# Blinky.net
KiCad netlist of a schematic drawn in EAGLE
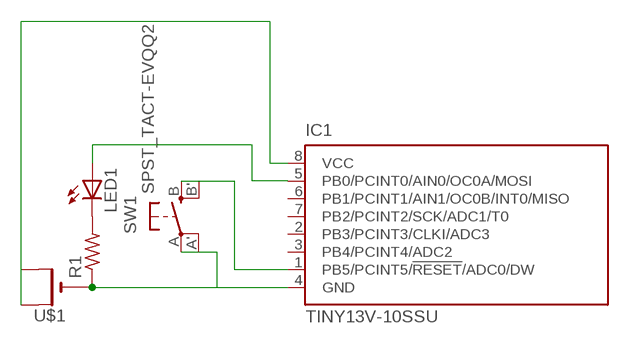
[diagram p0: schematic, sheet 1]

(export (version "E")
  (design (tool "Eeschema 10.0.6"))
  (components
    (comp (ref "IC1")
      (value "TINY13V-10SSU")
      (footprint "eagle-import:8S1")
      (fields
        (field (name "MPN") "ATTINY13V-10SSU")
        (field (name "MPN_1") "ATTINY13V-10SSU")
        (field (name "OC_FARNELL") "1455135")
        (field (name "OC_NEWARK") "58M3773")
      )
      (libsource (lib "eagle-import") (part "TINY13SSUV-10"))
    )
    (comp (ref "LED1")
      (value "LEDCHIPLED_1206")
      (footprint "eagle-import:CHIPLED_1206")
      (libsource (lib "eagle-import") (part "LEDCHIPLED_1206"))
    )
    (comp (ref "R1")
      (value "R-US_M1206")
      (footprint "eagle-import:M1206")
      (libsource (lib "eagle-import") (part "R-US_M1206"))
    )
    (comp (ref "SW1")
      (value "SPST_TACT-EVQQ2")
      (footprint "eagle-import:EVQ-Q2")
      (libsource (lib "eagle-import") (part "SPST_TACT-EVQQ2"))
    )
    (comp (ref "U$1")
      (value "CR1220SMT")
      (footprint "eagle-import:CR1220-SMD")
      (libsource (lib "eagle-import") (part "CR1220SMT"))
    )
  )
  (nets
    (net (code "1") (name "Net-(IC1-GND)") (class "Default")
      (node (ref "IC1") (pin "4") (pinfunction "GND_4") (pintype "power_in"))
      (node (ref "R1") (pin "1") (pinfunction "1_1") (pintype "passive"))
      (node (ref "SW1") (pin "A") (pinfunction "P_A") (pintype "passive"))
      (node (ref "SW1") (pin "A'") (pinfunction "P1_A'") (pintype "passive"))
      (node (ref "U$1") (pin "-") (pinfunction "-_-") (pintype "passive"))
    )
    (net (code "2") (name "Net-(IC1-PB0{slash}PCINT0{slash}AIN0{slash}OC0A{slash}MOSI)") (class "Default")
      (node (ref "IC1") (pin "5") (pinfunction "PB0/PCINT0/AIN0/OC0A/MOSI_5") (pintype "bidirectional"))
      (node (ref "LED1") (pin "A") (pinfunction "A_A") (pintype "passive"))
    )
    (net (code "3") (name "Net-(IC1-PB5{slash}PCINT5{slash}~{RESET}{slash}ADC0{slash}DW)") (class "Default")
      (node (ref "IC1") (pin "1") (pinfunction "PB5/PCINT5/~{RESET}/ADC0/DW_1") (pintype "bidirectional"))
      (node (ref "SW1") (pin "B") (pinfunction "S_B") (pintype "passive"))
    )
    (net (code "4") (name "Net-(IC1-VCC)") (class "Default")
      (node (ref "IC1") (pin "8") (pinfunction "VCC_8") (pintype "power_in"))
      (node (ref "U$1") (pin "+$1") (pinfunction "+_+$1") (pintype "passive"))
      (node (ref "U$1") (pin "+$2") (pinfunction "+1_+$2") (pintype "passive"))
    )
    (net (code "5") (name "Net-(LED1-PadC)") (class "Default")
      (node (ref "LED1") (pin "C") (pinfunction "C_C") (pintype "passive"))
      (node (ref "R1") (pin "2") (pinfunction "2_2") (pintype "passive"))
    )
    (net (code "6") (name "unconnected-(IC1-PB1{slash}PCINT1{slash}AIN1{slash}OC0B{slash}INT0{slash}MISO-Pad6)") (class "Default")
      (node (ref "IC1") (pin "6") (pinfunction "PB1/PCINT1/AIN1/OC0B/INT0/MISO_6") (pintype "bidirectional"))
    )
    (net (code "7") (name "unconnected-(IC1-PB2{slash}PCINT2{slash}SCK{slash}ADC1{slash}T0-Pad7)") (class "Default")
      (node (ref "IC1") (pin "7") (pinfunction "PB2/PCINT2/SCK/ADC1/T0_7") (pintype "bidirectional"))
    )
    (net (code "8") (name "unconnected-(IC1-PB3{slash}PCINT3{slash}CLKI{slash}ADC3-Pad2)") (class "Default")
      (node (ref "IC1") (pin "2") (pinfunction "PB3/PCINT3/CLKI/ADC3_2") (pintype "bidirectional"))
    )
    (net (code "9") (name "unconnected-(IC1-PB4{slash}PCINT4{slash}ADC2-Pad3)") (class "Default")
      (node (ref "IC1") (pin "3") (pinfunction "PB4/PCINT4/ADC2_3") (pintype "bidirectional"))
    )
    (net (code "10") (name "unconnected-(SW1-S1-PadB')") (class "Default")
      (node (ref "SW1") (pin "B'") (pinfunction "S1_B'") (pintype "passive"))
    )
  )
)
